# ADC.net
KiCad netlist of a schematic drawn in Altium Designer
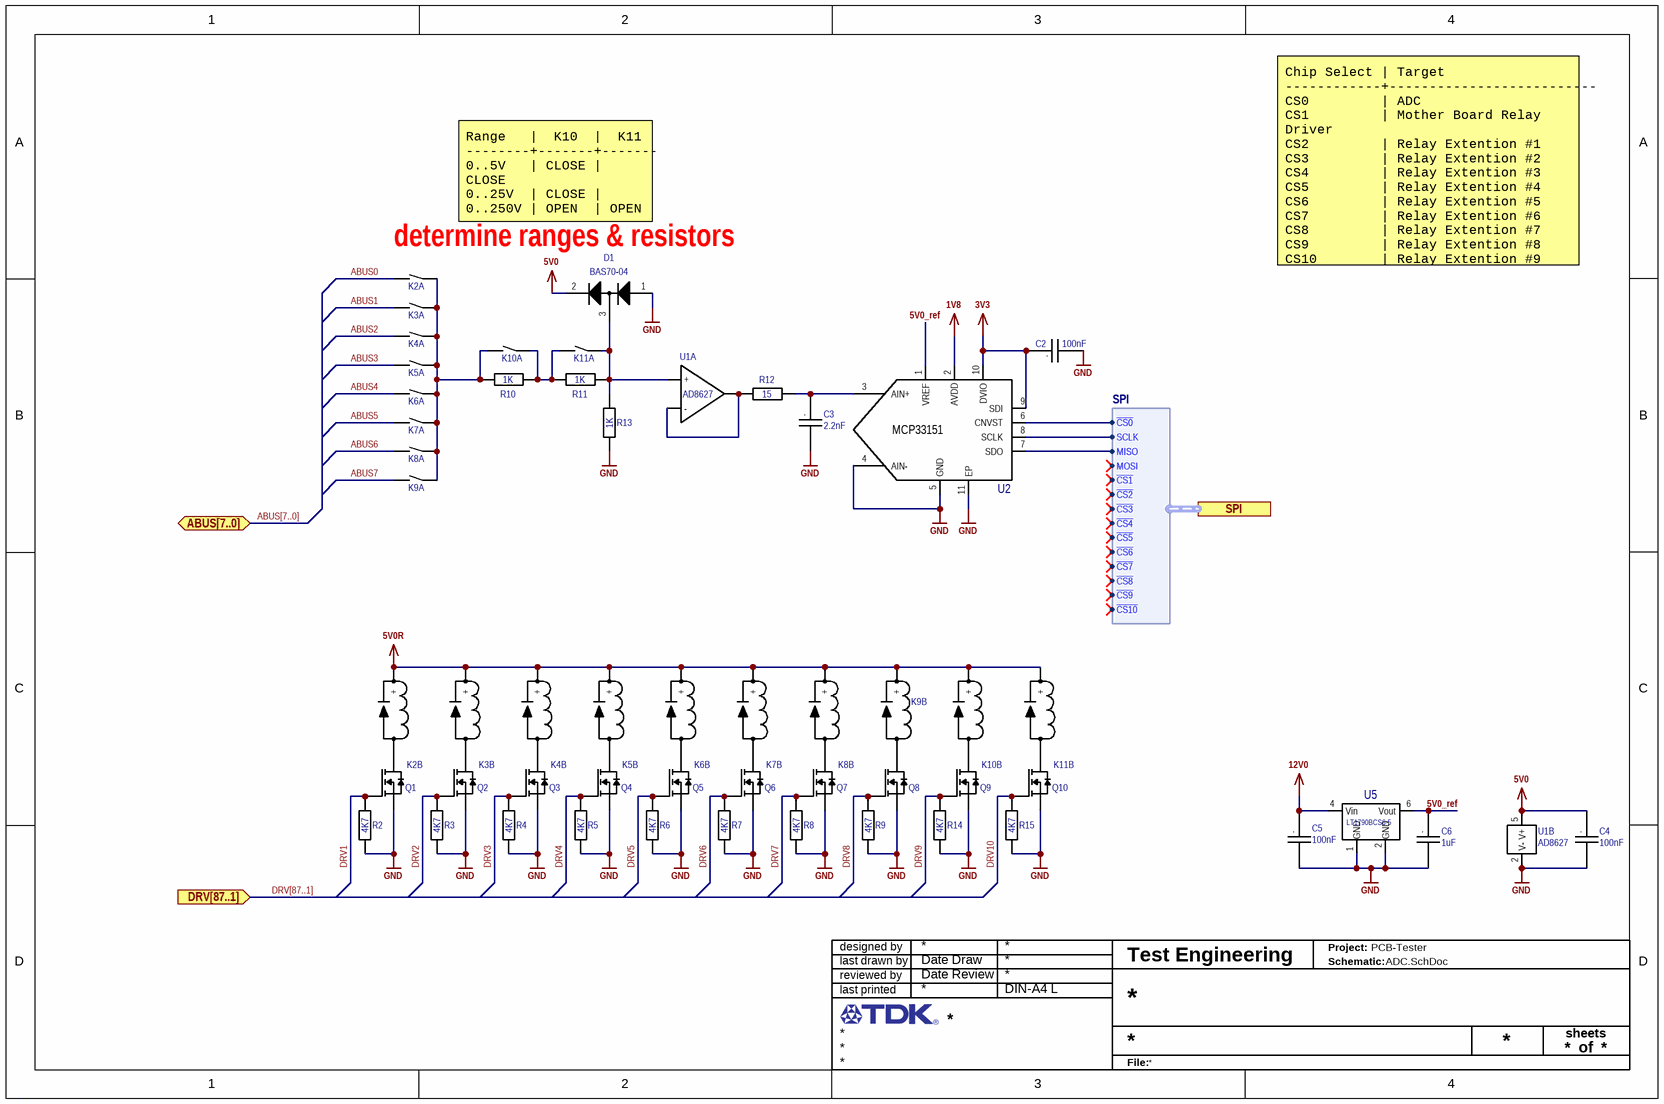
[diagram p0: ADC.SchDoc]

(export (version "E")
  (design (tool "Eeschema 10.0.6"))
  (components
    (comp (ref "C2")
      (value "100nF")
      (footprint "C0402 Reflow")
      (description "CAP CER 0.1UF 16V X7R 0402")
      (fields
        (field (name "TOLERANCE") "±5%")
        (field (name "02. DISTRIBUTOR PART NUMBER") "399-7761-6-ND")
        (field (name "13. CREATED DATE/NAME") "AUG2018/Hören")
      )
      (libsource (lib "chickenfood") (part "C"))
    )
    (comp (ref "C3")
      (value "2.2nF")
      (footprint "C0402 Reflow")
      (description "CAP CER 2200PF 50V X7R 0402")
      (fields
        (field (name "TOLERANCE") "±5%")
        (field (name "02. DISTRIBUTOR PART NUMBER") "1276-1532-6-ND")
        (field (name "13. CREATED DATE/NAME") "AUG2018/Hören")
      )
      (libsource (lib "chickenfood") (part "C"))
    )
    (comp (ref "C4")
      (value "100nF")
      (footprint "C0402 Reflow")
      (description "CAP CER 0.1UF 16V X7R 0402")
      (fields
        (field (name "TOLERANCE") "±5%")
        (field (name "02. DISTRIBUTOR PART NUMBER") "399-7761-6-ND")
        (field (name "13. CREATED DATE/NAME") "AUG2018/Hören")
      )
      (libsource (lib "chickenfood") (part "C"))
    )
    (comp (ref "C5")
      (value "100nF")
      (footprint "C0402 Reflow")
      (description "CAP CER 0.1UF 16V X7R 0402")
      (fields
        (field (name "TOLERANCE") "±5%")
        (field (name "02. DISTRIBUTOR PART NUMBER") "399-7761-6-ND")
        (field (name "13. CREATED DATE/NAME") "AUG2018/Hören")
      )
      (libsource (lib "chickenfood") (part "C"))
    )
    (comp (ref "C6")
      (value "1uF")
      (footprint "C0402 Reflow")
      (description "CAP CER 1UF 6.3V X7R 0402")
      (fields
        (field (name "TOLERANCE") "±10%")
        (field (name "02. DISTRIBUTOR PART NUMBER") "490-13339-6-ND")
        (field (name "13. CREATED DATE/NAME") "AUG2018/Hören")
      )
      (libsource (lib "chickenfood") (part "C"))
    )
    (comp (ref "D1")
      (value "D")
      (footprint "SOT23-3")
      (description "DIODE ARRAY SCHOTTKY 70V SOT23-3")
      (fields
        (field (name "02. DISTRIBUTOR PART NUMBER") "BAS70-04-FDITR-ND")
        (field (name "07. MANUFACTURER  PART NUMBER") "BAS70-04")
        (field (name "13. CREATED DATE/NAME") "AUG 2018 / Hören")
      )
      (libsource (lib "tom") (part "BAS70-04"))
    )
    (comp (ref "K2")
      (value "K")
      (footprint "118-1A")
      (description "5V Signal Relais, Normal Open")
      (fields
        (field (name "02. DISTRIBUTOR PART NUMBER") "118-1-A-5/2D")
        (field (name "13. CREATED DATE/NAME") "20.12.17 S. Kaiser")
      )
      (libsource (lib "chickenfood") (part "118-1-A-5/2D"))
    )
    (comp (ref "K3")
      (value "K")
      (footprint "118-1A")
      (description "5V Signal Relais, Normal Open")
      (fields
        (field (name "02. DISTRIBUTOR PART NUMBER") "118-1-A-5/2D")
        (field (name "13. CREATED DATE/NAME") "20.12.17 S. Kaiser")
      )
      (libsource (lib "chickenfood") (part "118-1-A-5/2D"))
    )
    (comp (ref "K4")
      (value "K")
      (footprint "118-1A")
      (description "5V Signal Relais, Normal Open")
      (fields
        (field (name "02. DISTRIBUTOR PART NUMBER") "118-1-A-5/2D")
        (field (name "13. CREATED DATE/NAME") "20.12.17 S. Kaiser")
      )
      (libsource (lib "chickenfood") (part "118-1-A-5/2D"))
    )
    (comp (ref "K5")
      (value "K")
      (footprint "118-1A")
      (description "5V Signal Relais, Normal Open")
      (fields
        (field (name "02. DISTRIBUTOR PART NUMBER") "118-1-A-5/2D")
        (field (name "13. CREATED DATE/NAME") "20.12.17 S. Kaiser")
      )
      (libsource (lib "chickenfood") (part "118-1-A-5/2D"))
    )
    (comp (ref "K6")
      (value "K")
      (footprint "118-1A")
      (description "5V Signal Relais, Normal Open")
      (fields
        (field (name "02. DISTRIBUTOR PART NUMBER") "118-1-A-5/2D")
        (field (name "13. CREATED DATE/NAME") "20.12.17 S. Kaiser")
      )
      (libsource (lib "chickenfood") (part "118-1-A-5/2D"))
    )
    (comp (ref "K7")
      (value "K")
      (footprint "118-1A")
      (description "5V Signal Relais, Normal Open")
      (fields
        (field (name "02. DISTRIBUTOR PART NUMBER") "118-1-A-5/2D")
        (field (name "13. CREATED DATE/NAME") "20.12.17 S. Kaiser")
      )
      (libsource (lib "chickenfood") (part "118-1-A-5/2D"))
    )
    (comp (ref "K8")
      (value "K")
      (footprint "118-1A")
      (description "5V Signal Relais, Normal Open")
      (fields
        (field (name "02. DISTRIBUTOR PART NUMBER") "118-1-A-5/2D")
        (field (name "13. CREATED DATE/NAME") "20.12.17 S. Kaiser")
      )
      (libsource (lib "chickenfood") (part "118-1-A-5/2D"))
    )
    (comp (ref "K9")
      (value "K")
      (footprint "118-1A")
      (description "5V Signal Relais, Normal Open")
      (fields
        (field (name "02. DISTRIBUTOR PART NUMBER") "118-1-A-5/2D")
        (field (name "13. CREATED DATE/NAME") "20.12.17 S. Kaiser")
      )
      (libsource (lib "chickenfood") (part "118-1-A-5/2D"))
    )
    (comp (ref "K10")
      (value "K")
      (footprint "118-1A")
      (description "5V Signal Relais, Normal Open")
      (fields
        (field (name "02. DISTRIBUTOR PART NUMBER") "118-1-A-5/2D")
        (field (name "13. CREATED DATE/NAME") "20.12.17 S. Kaiser")
      )
      (libsource (lib "chickenfood") (part "118-1-A-5/2D"))
    )
    (comp (ref "K11")
      (value "K")
      (footprint "118-1A")
      (description "5V Signal Relais, Normal Open")
      (fields
        (field (name "02. DISTRIBUTOR PART NUMBER") "118-1-A-5/2D")
        (field (name "13. CREATED DATE/NAME") "20.12.17 S. Kaiser")
      )
      (libsource (lib "chickenfood") (part "118-1-A-5/2D"))
    )
    (comp (ref "Q1")
      (value "Q")
      (footprint "SOT23-3")
      (description "MOSFET N-CH 25V 680MA SOT-23")
      (fields
        (field (name "02. DISTRIBUTOR PART NUMBER") "FDV303NDKR-ND")
        (field (name "07. MANUFACTURER  PART NUMBER") "FDV303N")
        (field (name "13. CREATED DATE/NAME") "AUG 2018 / Hören")
      )
      (libsource (lib "SCT8-Board1") (part "FDV303N"))
    )
    (comp (ref "Q2")
      (value "Q")
      (footprint "SOT23-3")
      (description "MOSFET N-CH 25V 680MA SOT-23")
      (fields
        (field (name "02. DISTRIBUTOR PART NUMBER") "FDV303NDKR-ND")
        (field (name "07. MANUFACTURER  PART NUMBER") "FDV303N")
        (field (name "13. CREATED DATE/NAME") "AUG 2018 / Hören")
      )
      (libsource (lib "SCT8-Board1") (part "FDV303N"))
    )
    (comp (ref "Q3")
      (value "Q")
      (footprint "SOT23-3")
      (description "MOSFET N-CH 25V 680MA SOT-23")
      (fields
        (field (name "02. DISTRIBUTOR PART NUMBER") "FDV303NDKR-ND")
        (field (name "07. MANUFACTURER  PART NUMBER") "FDV303N")
        (field (name "13. CREATED DATE/NAME") "AUG 2018 / Hören")
      )
      (libsource (lib "SCT8-Board1") (part "FDV303N"))
    )
    (comp (ref "Q4")
      (value "Q")
      (footprint "SOT23-3")
      (description "MOSFET N-CH 25V 680MA SOT-23")
      (fields
        (field (name "02. DISTRIBUTOR PART NUMBER") "FDV303NDKR-ND")
        (field (name "07. MANUFACTURER  PART NUMBER") "FDV303N")
        (field (name "13. CREATED DATE/NAME") "AUG 2018 / Hören")
      )
      (libsource (lib "SCT8-Board1") (part "FDV303N"))
    )
    (comp (ref "Q5")
      (value "Q")
      (footprint "SOT23-3")
      (description "MOSFET N-CH 25V 680MA SOT-23")
      (fields
        (field (name "02. DISTRIBUTOR PART NUMBER") "FDV303NDKR-ND")
        (field (name "07. MANUFACTURER  PART NUMBER") "FDV303N")
        (field (name "13. CREATED DATE/NAME") "AUG 2018 / Hören")
      )
      (libsource (lib "SCT8-Board1") (part "FDV303N"))
    )
    (comp (ref "Q6")
      (value "Q")
      (footprint "SOT23-3")
      (description "MOSFET N-CH 25V 680MA SOT-23")
      (fields
        (field (name "02. DISTRIBUTOR PART NUMBER") "FDV303NDKR-ND")
        (field (name "07. MANUFACTURER  PART NUMBER") "FDV303N")
        (field (name "13. CREATED DATE/NAME") "AUG 2018 / Hören")
      )
      (libsource (lib "SCT8-Board1") (part "FDV303N"))
    )
    (comp (ref "Q7")
      (value "Q")
      (footprint "SOT23-3")
      (description "MOSFET N-CH 25V 680MA SOT-23")
      (fields
        (field (name "02. DISTRIBUTOR PART NUMBER") "FDV303NDKR-ND")
        (field (name "07. MANUFACTURER  PART NUMBER") "FDV303N")
        (field (name "13. CREATED DATE/NAME") "AUG 2018 / Hören")
      )
      (libsource (lib "SCT8-Board1") (part "FDV303N"))
    )
    (comp (ref "Q8")
      (value "Q")
      (footprint "SOT23-3")
      (description "MOSFET N-CH 25V 680MA SOT-23")
      (fields
        (field (name "02. DISTRIBUTOR PART NUMBER") "FDV303NDKR-ND")
        (field (name "07. MANUFACTURER  PART NUMBER") "FDV303N")
        (field (name "13. CREATED DATE/NAME") "AUG 2018 / Hören")
      )
      (libsource (lib "SCT8-Board1") (part "FDV303N"))
    )
    (comp (ref "Q9")
      (value "Q")
      (footprint "SOT23-3")
      (description "MOSFET N-CH 25V 680MA SOT-23")
      (fields
        (field (name "02. DISTRIBUTOR PART NUMBER") "FDV303NDKR-ND")
        (field (name "07. MANUFACTURER  PART NUMBER") "FDV303N")
        (field (name "13. CREATED DATE/NAME") "AUG 2018 / Hören")
      )
      (libsource (lib "SCT8-Board1") (part "FDV303N"))
    )
    (comp (ref "Q10")
      (value "Q")
      (footprint "SOT23-3")
      (description "MOSFET N-CH 25V 680MA SOT-23")
      (fields
        (field (name "02. DISTRIBUTOR PART NUMBER") "FDV303NDKR-ND")
        (field (name "07. MANUFACTURER  PART NUMBER") "FDV303N")
        (field (name "13. CREATED DATE/NAME") "AUG 2018 / Hören")
      )
      (libsource (lib "SCT8-Board1") (part "FDV303N"))
    )
    (comp (ref "R2")
      (value "4K7")
      (footprint "R0402 Reflow")
      (description "Resistor")
      (fields
        (field (name "TOLERANCE") "±1%")
        (field (name "Comment") "R")
        (field (name "13. CREATED DATE/NAME") "AUG2018/Hören")
      )
      (libsource (lib "") (part "R_1"))
    )
    (comp (ref "R3")
      (value "4K7")
      (footprint "R0402 Reflow")
      (description "Resistor")
      (fields
        (field (name "TOLERANCE") "±1%")
        (field (name "Comment") "R")
        (field (name "13. CREATED DATE/NAME") "AUG2018/Hören")
      )
      (libsource (lib "") (part "R_1"))
    )
    (comp (ref "R4")
      (value "4K7")
      (footprint "R0402 Reflow")
      (description "Resistor")
      (fields
        (field (name "TOLERANCE") "±1%")
        (field (name "Comment") "R")
        (field (name "13. CREATED DATE/NAME") "AUG2018/Hören")
      )
      (libsource (lib "") (part "R_1"))
    )
    (comp (ref "R5")
      (value "4K7")
      (footprint "R0402 Reflow")
      (description "Resistor")
      (fields
        (field (name "TOLERANCE") "±1%")
        (field (name "Comment") "R")
        (field (name "13. CREATED DATE/NAME") "AUG2018/Hören")
      )
      (libsource (lib "") (part "R_1"))
    )
    (comp (ref "R6")
      (value "4K7")
      (footprint "R0402 Reflow")
      (description "Resistor")
      (fields
        (field (name "TOLERANCE") "±1%")
        (field (name "Comment") "R")
        (field (name "13. CREATED DATE/NAME") "AUG2018/Hören")
      )
      (libsource (lib "") (part "R_1"))
    )
    (comp (ref "R7")
      (value "4K7")
      (footprint "R0402 Reflow")
      (description "Resistor")
      (fields
        (field (name "TOLERANCE") "±1%")
        (field (name "Comment") "R")
        (field (name "13. CREATED DATE/NAME") "AUG2018/Hören")
      )
      (libsource (lib "") (part "R_1"))
    )
    (comp (ref "R8")
      (value "4K7")
      (footprint "R0402 Reflow")
      (description "Resistor")
      (fields
        (field (name "TOLERANCE") "±1%")
        (field (name "Comment") "R")
        (field (name "13. CREATED DATE/NAME") "AUG2018/Hören")
      )
      (libsource (lib "") (part "R_1"))
    )
    (comp (ref "R9")
      (value "4K7")
      (footprint "R0402 Reflow")
      (description "Resistor")
      (fields
        (field (name "TOLERANCE") "±1%")
        (field (name "Comment") "R")
        (field (name "13. CREATED DATE/NAME") "AUG2018/Hören")
      )
      (libsource (lib "") (part "R_1"))
    )
    (comp (ref "R10")
      (value "1K")
      (footprint "R0201 Reflow")
      (description "Resistor")
      (fields
        (field (name "TOLERANCE") "±1%")
        (field (name "Comment") "R")
        (field (name "13. CREATED DATE/NAME") "AUG2018/Hören")
      )
      (libsource (lib "chickenfood") (part "R"))
    )
    (comp (ref "R11")
      (value "1K")
      (footprint "R0201 Reflow")
      (description "Resistor")
      (fields
        (field (name "TOLERANCE") "±1%")
        (field (name "Comment") "R")
        (field (name "13. CREATED DATE/NAME") "AUG2018/Hören")
      )
      (libsource (lib "chickenfood") (part "R"))
    )
    (comp (ref "R12")
      (value "15")
      (footprint "R0402 Reflow")
      (description "RES SMD 15 OHM 1% 1/10W 0402")
      (fields
        (field (name "TOLERANCE") "±1%")
        (field (name "02. DISTRIBUTOR PART NUMBER") "P15.0LDKR-ND")
        (field (name "13. CREATED DATE/NAME") "AUG2018/Hören")
      )
      (libsource (lib "") (part "R_2"))
    )
    (comp (ref "R13")
      (value "1K")
      (footprint "R0201 Reflow")
      (description "Resistor")
      (fields
        (field (name "TOLERANCE") "±1%")
        (field (name "Comment") "R")
        (field (name "13. CREATED DATE/NAME") "AUG2018/Hören")
      )
      (libsource (lib "") (part "R_1"))
    )
    (comp (ref "R14")
      (value "4K7")
      (footprint "R0402 Reflow")
      (description "Resistor")
      (fields
        (field (name "TOLERANCE") "±1%")
        (field (name "Comment") "R")
        (field (name "13. CREATED DATE/NAME") "AUG2018/Hören")
      )
      (libsource (lib "") (part "R_1"))
    )
    (comp (ref "R15")
      (value "4K7")
      (footprint "R0402 Reflow")
      (description "Resistor")
      (fields
        (field (name "TOLERANCE") "±1%")
        (field (name "Comment") "R")
        (field (name "13. CREATED DATE/NAME") "AUG2018/Hören")
      )
      (libsource (lib "") (part "R_1"))
    )
    (comp (ref "U1")
      (value "U")
      (footprint "tom:SC70-5")
      (description "IC OPAMP JFET 5MHZ RRO SC70-5")
      (fields
        (field (name "02. DISTRIBUTOR PART NUMBER") "AD8627AKSZ-R2DKR-ND")
        (field (name "07. MANUFACTURER  PART NUMBER") "AD8627AKSZ-R2")
        (field (name "PART") "AD8627")
        (field (name "13. CREATED DATE/NAME") "AUG 2018 / Hören")
      )
      (libsource (lib "tom") (part "AD8627"))
    )
    (comp (ref "U2")
      (value "U")
      (footprint "TDFN10EP")
      (description "14-BIT 1 MSPS SGL CH SGL-ENDED S")
      (fields
        (field (name "02. DISTRIBUTOR PART NUMBER") "MCP33151-10T-E/MNDKR-ND")
        (field (name "07. MANUFACTURER  PART NUMBER") "MCP33151-10T-E/MN")
        (field (name "NICNAME") "MCP33151")
        (field (name "13. CREATED DATE/NAME") "AUG 2018 / Hören")
      )
      (libsource (lib "tom") (part "MCP33151-10T-E/MN"))
    )
    (comp (ref "U5")
      (value "U")
      (footprint "TSOT23-6(S6)")
      (description "IC VREF SERIES 5V, 0.1% TSOT-23-6")
      (fields
        (field (name "02. DISTRIBUTOR PART NUMBER") "LT1790BCS6-5#TRMPBFDKR-ND")
        (field (name "07. MANUFACTURER  PART NUMBER") "LT1790BCS6-5#TRMPBF")
        (field (name "NICNAME") "LT1790BCS6-5")
        (field (name "13. CREATED DATE/NAME") "AUG 2018 / Hören")
      )
      (libsource (lib "tom") (part "LT1790BCS6-5"))
    )
  )
  (nets
    (net (code "79") (name "/5V0_ref") (class "Default")
      (node (ref "C6") (pin "1") (pinfunction "1_1") (pintype "passive"))
      (node (ref "U2") (pin "1") (pinfunction "VREF_1") (pintype "passive"))
      (node (ref "U5") (pin "6") (pinfunction "Vout_6") (pintype "passive"))
    )
    (net (code "80") (name "/ABUS0") (class "Default")
      (node (ref "K2") (pin "3") (pinfunction "CA_3") (pintype "passive"))
    )
    (net (code "81") (name "/ABUS1") (class "Default")
      (node (ref "K3") (pin "3") (pinfunction "CA_3") (pintype "passive"))
    )
    (net (code "82") (name "/ABUS2") (class "Default")
      (node (ref "K4") (pin "3") (pinfunction "CA_3") (pintype "passive"))
    )
    (net (code "83") (name "/ABUS3") (class "Default")
      (node (ref "K5") (pin "3") (pinfunction "CA_3") (pintype "passive"))
    )
    (net (code "84") (name "/ABUS4") (class "Default")
      (node (ref "K6") (pin "3") (pinfunction "CA_3") (pintype "passive"))
    )
    (net (code "85") (name "/ABUS5") (class "Default")
      (node (ref "K7") (pin "3") (pinfunction "CA_3") (pintype "passive"))
    )
    (net (code "86") (name "/ABUS6") (class "Default")
      (node (ref "K8") (pin "3") (pinfunction "CA_3") (pintype "passive"))
    )
    (net (code "87") (name "/ABUS7") (class "Default")
      (node (ref "K9") (pin "3") (pinfunction "CA_3") (pintype "passive"))
    )
    (net (code "89") (name "/DRV1") (class "Default")
      (node (ref "Q1") (pin "1") (pinfunction "G_1") (pintype "passive"))
      (node (ref "R2") (pin "2") (pinfunction "2_2") (pintype "passive"))
    )
    (net (code "90") (name "/DRV2") (class "Default")
      (node (ref "Q2") (pin "1") (pinfunction "G_1") (pintype "passive"))
      (node (ref "R3") (pin "2") (pinfunction "2_2") (pintype "passive"))
    )
    (net (code "91") (name "/DRV3") (class "Default")
      (node (ref "Q3") (pin "1") (pinfunction "G_1") (pintype "passive"))
      (node (ref "R4") (pin "2") (pinfunction "2_2") (pintype "passive"))
    )
    (net (code "92") (name "/DRV4") (class "Default")
      (node (ref "Q4") (pin "1") (pinfunction "G_1") (pintype "passive"))
      (node (ref "R5") (pin "2") (pinfunction "2_2") (pintype "passive"))
    )
    (net (code "93") (name "/DRV5") (class "Default")
      (node (ref "Q5") (pin "1") (pinfunction "G_1") (pintype "passive"))
      (node (ref "R6") (pin "2") (pinfunction "2_2") (pintype "passive"))
    )
    (net (code "94") (name "/DRV6") (class "Default")
      (node (ref "Q6") (pin "1") (pinfunction "G_1") (pintype "passive"))
      (node (ref "R7") (pin "2") (pinfunction "2_2") (pintype "passive"))
    )
    (net (code "95") (name "/DRV7") (class "Default")
      (node (ref "Q7") (pin "1") (pinfunction "G_1") (pintype "passive"))
      (node (ref "R8") (pin "2") (pinfunction "2_2") (pintype "passive"))
    )
    (net (code "96") (name "/DRV8") (class "Default")
      (node (ref "Q8") (pin "1") (pinfunction "G_1") (pintype "passive"))
      (node (ref "R9") (pin "2") (pinfunction "2_2") (pintype "passive"))
    )
    (net (code "97") (name "/DRV9") (class "Default")
      (node (ref "Q9") (pin "1") (pinfunction "G_1") (pintype "passive"))
      (node (ref "R14") (pin "2") (pinfunction "2_2") (pintype "passive"))
    )
    (net (code "98") (name "/DRV10") (class "Default")
      (node (ref "Q10") (pin "1") (pinfunction "G_1") (pintype "passive"))
      (node (ref "R15") (pin "2") (pinfunction "2_2") (pintype "passive"))
    )
    (net (code "100") (name "/MISO") (class "Default")
      (node (ref "U2") (pin "7") (pinfunction "SDO_7") (pintype "passive"))
    )
    (net (code "101") (name "/SCLK") (class "Default")
      (node (ref "U2") (pin "8") (pinfunction "SCLK_8") (pintype "passive"))
    )
    (net (code "103") (name "/~{CS0}") (class "Default")
      (node (ref "U2") (pin "6") (pinfunction "CNVST_6") (pintype "passive"))
    )
    (net (code "104") (name "1V8") (class "Default")
      (node (ref "U2") (pin "2") (pinfunction "AVDD_2") (pintype "passive"))
    )
    (net (code "105") (name "3V3") (class "Default")
      (node (ref "C2") (pin "1") (pinfunction "1_1") (pintype "passive"))
      (node (ref "U2") (pin "10") (pinfunction "DVIO_10") (pintype "passive"))
      (node (ref "U2") (pin "9") (pinfunction "SDI_9") (pintype "passive"))
    )
    (net (code "106") (name "5V0") (class "Default")
      (node (ref "C4") (pin "1") (pinfunction "1_1") (pintype "passive"))
      (node (ref "D1") (pin "2") (pinfunction "2_2") (pintype "passive"))
      (node (ref "U1") (pin "5") (pinfunction "V+_5") (pintype "passive"))
    )
    (net (code "107") (name "5V0R") (class "Default")
      (node (ref "K10") (pin "1") (pinfunction "+_1") (pintype "passive"))
      (node (ref "K11") (pin "1") (pinfunction "+_1") (pintype "passive"))
      (node (ref "K2") (pin "1") (pinfunction "+_1") (pintype "passive"))
      (node (ref "K3") (pin "1") (pinfunction "+_1") (pintype "passive"))
      (node (ref "K4") (pin "1") (pinfunction "+_1") (pintype "passive"))
      (node (ref "K5") (pin "1") (pinfunction "+_1") (pintype "passive"))
      (node (ref "K6") (pin "1") (pinfunction "+_1") (pintype "passive"))
      (node (ref "K7") (pin "1") (pinfunction "+_1") (pintype "passive"))
      (node (ref "K8") (pin "1") (pinfunction "+_1") (pintype "passive"))
      (node (ref "K9") (pin "1") (pinfunction "+_1") (pintype "passive"))
    )
    (net (code "108") (name "12V0") (class "Default")
      (node (ref "C5") (pin "1") (pinfunction "1_1") (pintype "passive"))
      (node (ref "U5") (pin "4") (pinfunction "Vin_4") (pintype "passive"))
    )
    (net (code "109") (name "GND") (class "Default")
      (node (ref "C2") (pin "2") (pinfunction "2_2") (pintype "passive"))
      (node (ref "C3") (pin "2") (pinfunction "2_2") (pintype "passive"))
      (node (ref "C4") (pin "2") (pinfunction "2_2") (pintype "passive"))
      (node (ref "C5") (pin "2") (pinfunction "2_2") (pintype "passive"))
      (node (ref "C6") (pin "2") (pinfunction "2_2") (pintype "passive"))
      (node (ref "D1") (pin "1") (pinfunction "1_1") (pintype "passive"))
      (node (ref "Q1") (pin "2") (pinfunction "S_2") (pintype "passive"))
      (node (ref "Q10") (pin "2") (pinfunction "S_2") (pintype "passive"))
      (node (ref "Q2") (pin "2") (pinfunction "S_2") (pintype "passive"))
      (node (ref "Q3") (pin "2") (pinfunction "S_2") (pintype "passive"))
      (node (ref "Q4") (pin "2") (pinfunction "S_2") (pintype "passive"))
      (node (ref "Q5") (pin "2") (pinfunction "S_2") (pintype "passive"))
      (node (ref "Q6") (pin "2") (pinfunction "S_2") (pintype "passive"))
      (node (ref "Q7") (pin "2") (pinfunction "S_2") (pintype "passive"))
      (node (ref "Q8") (pin "2") (pinfunction "S_2") (pintype "passive"))
      (node (ref "Q9") (pin "2") (pinfunction "S_2") (pintype "passive"))
      (node (ref "R13") (pin "1") (pinfunction "1_1") (pintype "passive"))
      (node (ref "R14") (pin "1") (pinfunction "1_1") (pintype "passive"))
      (node (ref "R15") (pin "1") (pinfunction "1_1") (pintype "passive"))
      (node (ref "R2") (pin "1") (pinfunction "1_1") (pintype "passive"))
      (node (ref "R3") (pin "1") (pinfunction "1_1") (pintype "passive"))
      (node (ref "R4") (pin "1") (pinfunction "1_1") (pintype "passive"))
      (node (ref "R5") (pin "1") (pinfunction "1_1") (pintype "passive"))
      (node (ref "R6") (pin "1") (pinfunction "1_1") (pintype "passive"))
      (node (ref "R7") (pin "1") (pinfunction "1_1") (pintype "passive"))
      (node (ref "R8") (pin "1") (pinfunction "1_1") (pintype "passive"))
      (node (ref "R9") (pin "1") (pinfunction "1_1") (pintype "passive"))
      (node (ref "U1") (pin "2") (pinfunction "V-_2") (pintype "passive"))
      (node (ref "U2") (pin "11") (pinfunction "EP_11") (pintype "passive"))
      (node (ref "U2") (pin "4") (pinfunction "AIN-_4") (pintype "passive"))
      (node (ref "U2") (pin "5") (pinfunction "GND_5") (pintype "passive"))
      (node (ref "U5") (pin "1") (pinfunction "GND_1") (pintype "passive"))
      (node (ref "U5") (pin "2") (pinfunction "GND_2") (pintype "passive"))
    )
    (net (code "110") (name "Net-(K2B--)") (class "Default")
      (node (ref "K2") (pin "2") (pinfunction "-_2") (pintype "passive"))
      (node (ref "Q1") (pin "3") (pinfunction "D_3") (pintype "passive"))
    )
    (net (code "111") (name "Net-(K3B--)") (class "Default")
      (node (ref "K3") (pin "2") (pinfunction "-_2") (pintype "passive"))
      (node (ref "Q2") (pin "3") (pinfunction "D_3") (pintype "passive"))
    )
    (net (code "112") (name "Net-(K4B--)") (class "Default")
      (node (ref "K4") (pin "2") (pinfunction "-_2") (pintype "passive"))
      (node (ref "Q3") (pin "3") (pinfunction "D_3") (pintype "passive"))
    )
    (net (code "113") (name "Net-(K5B--)") (class "Default")
      (node (ref "K5") (pin "2") (pinfunction "-_2") (pintype "passive"))
      (node (ref "Q4") (pin "3") (pinfunction "D_3") (pintype "passive"))
    )
    (net (code "114") (name "Net-(K6B--)") (class "Default")
      (node (ref "K6") (pin "2") (pinfunction "-_2") (pintype "passive"))
      (node (ref "Q5") (pin "3") (pinfunction "D_3") (pintype "passive"))
    )
    (net (code "115") (name "Net-(K7B--)") (class "Default")
      (node (ref "K7") (pin "2") (pinfunction "-_2") (pintype "passive"))
      (node (ref "Q6") (pin "3") (pinfunction "D_3") (pintype "passive"))
    )
    (net (code "116") (name "Net-(K8B--)") (class "Default")
      (node (ref "K8") (pin "2") (pinfunction "-_2") (pintype "passive"))
      (node (ref "Q7") (pin "3") (pinfunction "D_3") (pintype "passive"))
    )
    (net (code "117") (name "Net-(K9B--)") (class "Default")
      (node (ref "K9") (pin "2") (pinfunction "-_2") (pintype "passive"))
      (node (ref "Q8") (pin "3") (pinfunction "D_3") (pintype "passive"))
    )
    (net (code "118") (name "Net-(K10A-CA)") (class "Default")
      (node (ref "K10") (pin "3") (pinfunction "CA_3") (pintype "passive"))
      (node (ref "K2") (pin "4") (pinfunction "CB_4") (pintype "passive"))
      (node (ref "K3") (pin "4") (pinfunction "CB_4") (pintype "passive"))
      (node (ref "K4") (pin "4") (pinfunction "CB_4") (pintype "passive"))
      (node (ref "K5") (pin "4") (pinfunction "CB_4") (pintype "passive"))
      (node (ref "K6") (pin "4") (pinfunction "CB_4") (pintype "passive"))
      (node (ref "K7") (pin "4") (pinfunction "CB_4") (pintype "passive"))
      (node (ref "K8") (pin "4") (pinfunction "CB_4") (pintype "passive"))
      (node (ref "K9") (pin "4") (pinfunction "CB_4") (pintype "passive"))
      (node (ref "R10") (pin "1") (pinfunction "1_1") (pintype "passive"))
    )
    (net (code "119") (name "Net-(K10A-CB)") (class "Default")
      (node (ref "K10") (pin "4") (pinfunction "CB_4") (pintype "passive"))
      (node (ref "K11") (pin "3") (pinfunction "CA_3") (pintype "passive"))
      (node (ref "R10") (pin "2") (pinfunction "2_2") (pintype "passive"))
      (node (ref "R11") (pin "1") (pinfunction "1_1") (pintype "passive"))
    )
    (net (code "120") (name "Net-(K10B--)") (class "Default")
      (node (ref "K10") (pin "2") (pinfunction "-_2") (pintype "passive"))
      (node (ref "Q9") (pin "3") (pinfunction "D_3") (pintype "passive"))
    )
    (net (code "121") (name "Net-(K11A-CB)") (class "Default")
      (node (ref "D1") (pin "3") (pinfunction "3_3") (pintype "passive"))
      (node (ref "K11") (pin "4") (pinfunction "CB_4") (pintype "passive"))
      (node (ref "R11") (pin "2") (pinfunction "2_2") (pintype "passive"))
      (node (ref "R13") (pin "2") (pinfunction "2_2") (pintype "passive"))
      (node (ref "U1") (pin "3") (pinfunction "+_3") (pintype "passive"))
    )
    (net (code "122") (name "Net-(K11B--)") (class "Default")
      (node (ref "K11") (pin "2") (pinfunction "-_2") (pintype "passive"))
      (node (ref "Q10") (pin "3") (pinfunction "D_3") (pintype "passive"))
    )
    (net (code "123") (name "Net-(U1A--)") (class "Default")
      (node (ref "R12") (pin "2") (pinfunction "2_2") (pintype "passive"))
      (node (ref "U1") (pin "1") (pinfunction "Out_1") (pintype "passive"))
      (node (ref "U1") (pin "4") (pinfunction "-_4") (pintype "passive"))
    )
    (net (code "124") (name "Net-(U2-AIN+)") (class "Default")
      (node (ref "C3") (pin "1") (pinfunction "1_1") (pintype "passive"))
      (node (ref "R12") (pin "1") (pinfunction "1_1") (pintype "passive"))
      (node (ref "U2") (pin "3") (pinfunction "AIN+_3") (pintype "passive"))
    )
  )
)
